# 2dolvlBUP.net
KiCad netlist of a schematic drawn in EAGLE
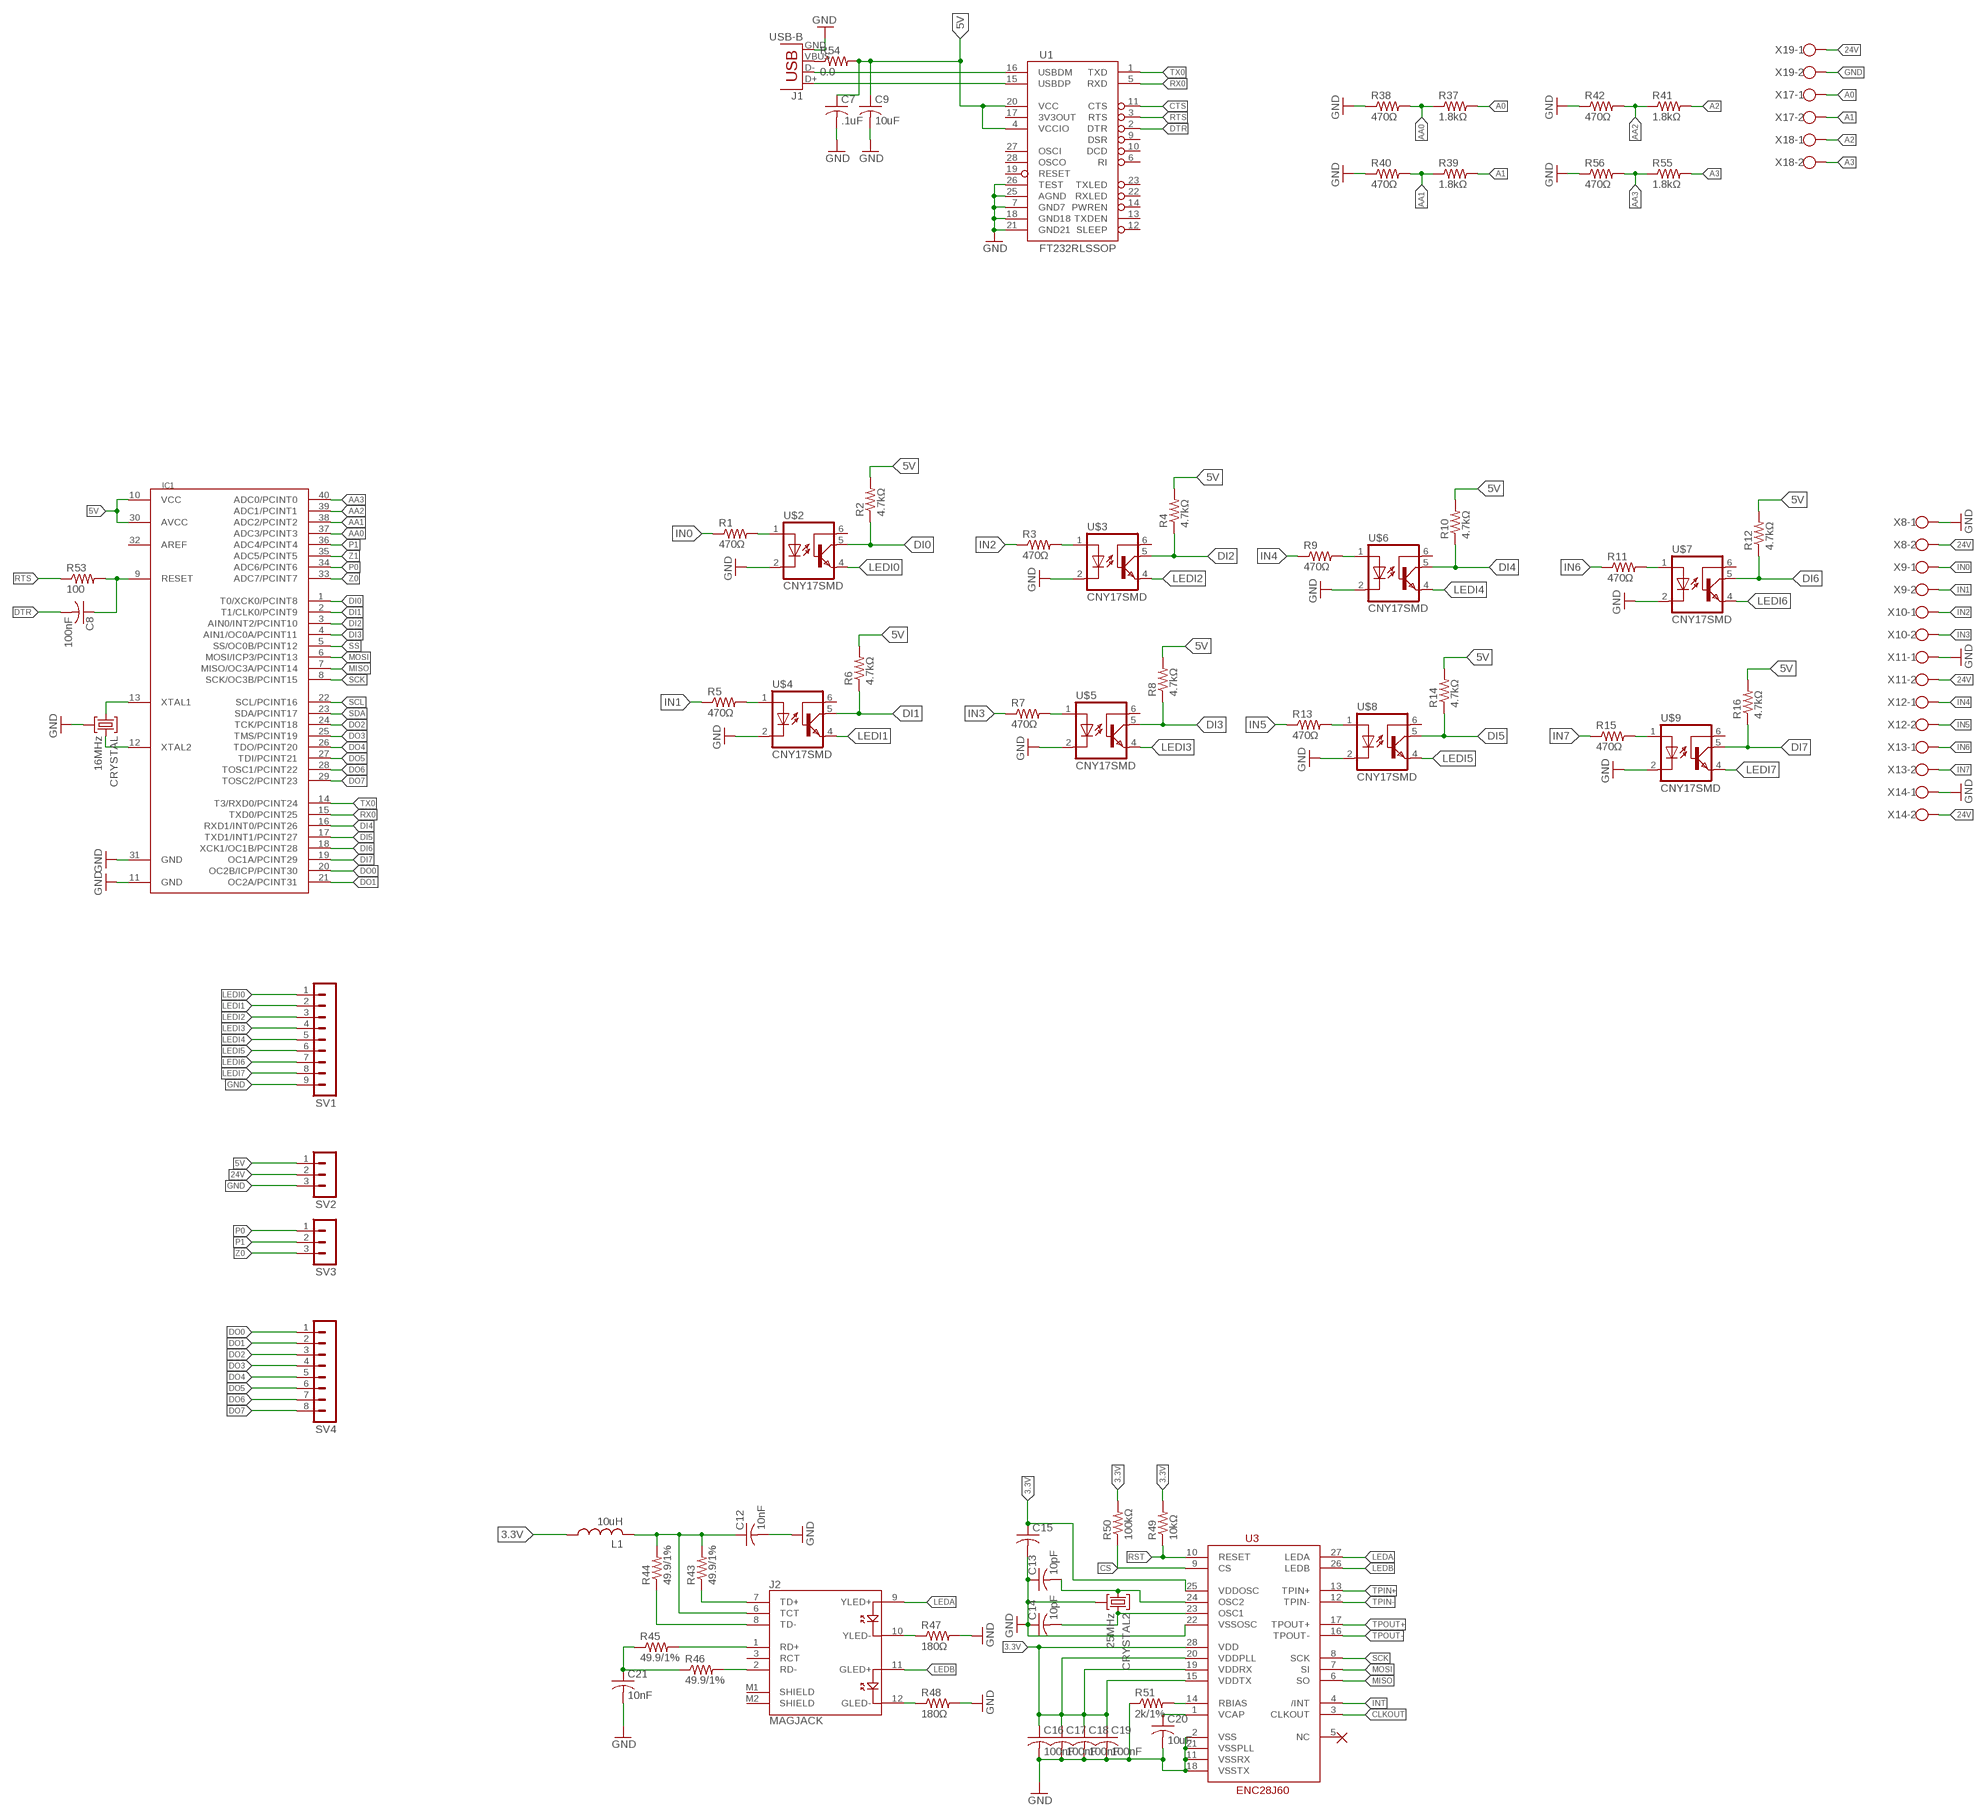
[diagram p0: schematic, sheet 1]

(export (version "E")
  (design (tool "Eeschema 10.0.6"))
  (components
    (comp (ref "C7")
      (value ".1uF")
      (footprint "eagle-import:C0402K")
      (libsource (lib "eagle-import") (part "C-USC0402K"))
    )
    (comp (ref "C8")
      (value "100nF")
      (footprint "eagle-import:C025-025X050")
      (libsource (lib "eagle-import") (part "C-US025-025X050"))
    )
    (comp (ref "C9")
      (value "10uF")
      (footprint "eagle-import:C0805K")
      (libsource (lib "eagle-import") (part "C-USC0805K"))
    )
    (comp (ref "C12")
      (value "10nF")
      (footprint "eagle-import:C0402K")
      (libsource (lib "eagle-import") (part "C-USC0402K"))
    )
    (comp (ref "C13")
      (value "10pF")
      (footprint "eagle-import:C0603K")
      (libsource (lib "eagle-import") (part "C-USC0603K"))
    )
    (comp (ref "C14")
      (value "10pF")
      (footprint "eagle-import:C0603K")
      (libsource (lib "eagle-import") (part "C-USC0603K"))
    )
    (comp (ref "C15")
      (value "C-US025-025X050")
      (footprint "eagle-import:C025-025X050")
      (libsource (lib "eagle-import") (part "C-US025-025X050"))
    )
    (comp (ref "C16")
      (value "100nF")
      (footprint "eagle-import:C025-025X050")
      (libsource (lib "eagle-import") (part "C-US025-025X050"))
    )
    (comp (ref "C17")
      (value "100nF")
      (footprint "eagle-import:C025-025X050")
      (libsource (lib "eagle-import") (part "C-US025-025X050"))
    )
    (comp (ref "C18")
      (value "100nF")
      (footprint "eagle-import:C025-025X050")
      (libsource (lib "eagle-import") (part "C-US025-025X050"))
    )
    (comp (ref "C19")
      (value "100nF")
      (footprint "eagle-import:C025-025X050")
      (libsource (lib "eagle-import") (part "C-US025-025X050"))
    )
    (comp (ref "C20")
      (value "10uF")
      (footprint "eagle-import:C0805K")
      (libsource (lib "eagle-import") (part "C-USC0805K"))
    )
    (comp (ref "C21")
      (value "10nF")
      (footprint "eagle-import:C0402K")
      (libsource (lib "eagle-import") (part "C-USC0402K"))
    )
    (comp (ref "CRYSTAL")
      (value "16MHz")
      (footprint "eagle-import:SMDCRYSTAL")
      (libsource (lib "eagle-import") (part "SMDCRYSTAL"))
    )
    (comp (ref "CRYSTAL2")
      (value "25MHz")
      (footprint "eagle-import:SMDCRYSTAL")
      (libsource (lib "eagle-import") (part "SMDCRYSTAL"))
    )
    (comp (ref "IC1")
      (value "MEGA1284P")
      (footprint "eagle-import:DIL40")
      (libsource (lib "eagle-import") (part "MEGA1284P"))
    )
    (comp (ref "J1")
      (value "USB-B")
      (footprint "eagle-import:USB-B-PTH")
      (libsource (lib "eagle-import") (part "USBPTH"))
    )
    (comp (ref "J2")
      (value "MAGJACK")
      (footprint "eagle-import:MAGJACK")
      (libsource (lib "eagle-import") (part "MAGJACK"))
    )
    (comp (ref "L1")
      (value "10uH")
      (footprint "eagle-import:0204_7")
      (libsource (lib "eagle-import") (part "L-US0204/7"))
    )
    (comp (ref "R1")
      (value "470Ω")
      (footprint "eagle-import:M0805")
      (libsource (lib "eagle-import") (part "R-US_M0805"))
    )
    (comp (ref "R2")
      (value "4.7kΩ")
      (footprint "eagle-import:M1206")
      (libsource (lib "eagle-import") (part "R-US_M1206"))
    )
    (comp (ref "R3")
      (value "470Ω")
      (footprint "eagle-import:M0805")
      (libsource (lib "eagle-import") (part "R-US_M0805"))
    )
    (comp (ref "R4")
      (value "4.7kΩ")
      (footprint "eagle-import:M1206")
      (libsource (lib "eagle-import") (part "R-US_M1206"))
    )
    (comp (ref "R5")
      (value "470Ω")
      (footprint "eagle-import:M0805")
      (libsource (lib "eagle-import") (part "R-US_M0805"))
    )
    (comp (ref "R6")
      (value "4.7kΩ")
      (footprint "eagle-import:M1206")
      (libsource (lib "eagle-import") (part "R-US_M1206"))
    )
    (comp (ref "R7")
      (value "470Ω")
      (footprint "eagle-import:M0805")
      (libsource (lib "eagle-import") (part "R-US_M0805"))
    )
    (comp (ref "R8")
      (value "4.7kΩ")
      (footprint "eagle-import:M1206")
      (libsource (lib "eagle-import") (part "R-US_M1206"))
    )
    (comp (ref "R9")
      (value "470Ω")
      (footprint "eagle-import:M0805")
      (libsource (lib "eagle-import") (part "R-US_M0805"))
    )
    (comp (ref "R10")
      (value "4.7kΩ")
      (footprint "eagle-import:M1206")
      (libsource (lib "eagle-import") (part "R-US_M1206"))
    )
    (comp (ref "R11")
      (value "470Ω")
      (footprint "eagle-import:M0805")
      (libsource (lib "eagle-import") (part "R-US_M0805"))
    )
    (comp (ref "R12")
      (value "4.7kΩ")
      (footprint "eagle-import:M1206")
      (libsource (lib "eagle-import") (part "R-US_M1206"))
    )
    (comp (ref "R13")
      (value "470Ω")
      (footprint "eagle-import:M0805")
      (libsource (lib "eagle-import") (part "R-US_M0805"))
    )
    (comp (ref "R14")
      (value "4.7kΩ")
      (footprint "eagle-import:M1206")
      (libsource (lib "eagle-import") (part "R-US_M1206"))
    )
    (comp (ref "R15")
      (value "470Ω")
      (footprint "eagle-import:M0805")
      (libsource (lib "eagle-import") (part "R-US_M0805"))
    )
    (comp (ref "R16")
      (value "4.7kΩ")
      (footprint "eagle-import:M1206")
      (libsource (lib "eagle-import") (part "R-US_M1206"))
    )
    (comp (ref "R37")
      (value "1.8kΩ")
      (footprint "eagle-import:M0805")
      (libsource (lib "eagle-import") (part "R-US_M0805"))
    )
    (comp (ref "R38")
      (value "470Ω")
      (footprint "eagle-import:M0805")
      (libsource (lib "eagle-import") (part "R-US_M0805"))
    )
    (comp (ref "R39")
      (value "1.8kΩ")
      (footprint "eagle-import:M0805")
      (libsource (lib "eagle-import") (part "R-US_M0805"))
    )
    (comp (ref "R40")
      (value "470Ω")
      (footprint "eagle-import:M0805")
      (libsource (lib "eagle-import") (part "R-US_M0805"))
    )
    (comp (ref "R41")
      (value "1.8kΩ")
      (footprint "eagle-import:M0805")
      (libsource (lib "eagle-import") (part "R-US_M0805"))
    )
    (comp (ref "R42")
      (value "470Ω")
      (footprint "eagle-import:M0805")
      (libsource (lib "eagle-import") (part "R-US_M0805"))
    )
    (comp (ref "R43")
      (value "49.9/1%")
      (footprint "eagle-import:R0402")
      (libsource (lib "eagle-import") (part "R-US_R0402"))
    )
    (comp (ref "R44")
      (value "49.9/1%")
      (footprint "eagle-import:R0402")
      (libsource (lib "eagle-import") (part "R-US_R0402"))
    )
    (comp (ref "R45")
      (value "49.9/1%")
      (footprint "eagle-import:R0402")
      (libsource (lib "eagle-import") (part "R-US_R0402"))
    )
    (comp (ref "R46")
      (value "49.9/1%")
      (footprint "eagle-import:R0402")
      (libsource (lib "eagle-import") (part "R-US_R0402"))
    )
    (comp (ref "R47")
      (value "180Ω")
      (footprint "eagle-import:M0805")
      (libsource (lib "eagle-import") (part "R-US_M0805"))
    )
    (comp (ref "R48")
      (value "180Ω")
      (footprint "eagle-import:M0805")
      (libsource (lib "eagle-import") (part "R-US_M0805"))
    )
    (comp (ref "R49")
      (value "10kΩ")
      (footprint "eagle-import:R0402")
      (libsource (lib "eagle-import") (part "R-US_R0402"))
    )
    (comp (ref "R50")
      (value "100kΩ")
      (footprint "eagle-import:R0603")
      (libsource (lib "eagle-import") (part "R-US_R0603"))
    )
    (comp (ref "R51")
      (value "2k/1%")
      (footprint "eagle-import:R0603")
      (libsource (lib "eagle-import") (part "R-US_R0603"))
    )
    (comp (ref "R53")
      (value "100")
      (footprint "eagle-import:1206")
      (libsource (lib "eagle-import") (part "RESISTOR1206"))
    )
    (comp (ref "R54")
      (value "0.0")
      (footprint "eagle-import:1206")
      (libsource (lib "eagle-import") (part "RESISTOR1206"))
    )
    (comp (ref "R55")
      (value "1.8kΩ")
      (footprint "eagle-import:M0805")
      (libsource (lib "eagle-import") (part "R-US_M0805"))
    )
    (comp (ref "R56")
      (value "470Ω")
      (footprint "eagle-import:M0805")
      (libsource (lib "eagle-import") (part "R-US_M0805"))
    )
    (comp (ref "SV1")
      (value "MA09-1")
      (footprint "eagle-import:MA09-1")
      (libsource (lib "eagle-import") (part "MA09-1"))
    )
    (comp (ref "SV2")
      (value "MA03-1")
      (footprint "eagle-import:MA03-1")
      (libsource (lib "eagle-import") (part "MA03-1"))
    )
    (comp (ref "SV3")
      (value "MA03-1")
      (footprint "eagle-import:MA03-1")
      (libsource (lib "eagle-import") (part "MA03-1"))
    )
    (comp (ref "SV4")
      (value "MA08-1")
      (footprint "eagle-import:MA08-1")
      (libsource (lib "eagle-import") (part "MA08-1"))
    )
    (comp (ref "U$2")
      (value "CNY17SMD")
      (footprint "eagle-import:DIL6-SMD")
      (libsource (lib "eagle-import") (part "CNY17SMD"))
    )
    (comp (ref "U$3")
      (value "CNY17SMD")
      (footprint "eagle-import:DIL6-SMD")
      (libsource (lib "eagle-import") (part "CNY17SMD"))
    )
    (comp (ref "U$4")
      (value "CNY17SMD")
      (footprint "eagle-import:DIL6-SMD")
      (libsource (lib "eagle-import") (part "CNY17SMD"))
    )
    (comp (ref "U$5")
      (value "CNY17SMD")
      (footprint "eagle-import:DIL6-SMD")
      (libsource (lib "eagle-import") (part "CNY17SMD"))
    )
    (comp (ref "U$6")
      (value "CNY17SMD")
      (footprint "eagle-import:DIL6-SMD")
      (libsource (lib "eagle-import") (part "CNY17SMD"))
    )
    (comp (ref "U$7")
      (value "CNY17SMD")
      (footprint "eagle-import:DIL6-SMD")
      (libsource (lib "eagle-import") (part "CNY17SMD"))
    )
    (comp (ref "U$8")
      (value "CNY17SMD")
      (footprint "eagle-import:DIL6-SMD")
      (libsource (lib "eagle-import") (part "CNY17SMD"))
    )
    (comp (ref "U$9")
      (value "CNY17SMD")
      (footprint "eagle-import:DIL6-SMD")
      (libsource (lib "eagle-import") (part "CNY17SMD"))
    )
    (comp (ref "U1")
      (value "FT232RLSSOP")
      (footprint "eagle-import:SSOP28DB")
      (libsource (lib "eagle-import") (part "FT232RLSSOP"))
    )
    (comp (ref "U3")
      (value "ENC28J60")
      (footprint "eagle-import:SSOP28DB")
      (libsource (lib "eagle-import") (part "ENC28J60"))
    )
    (comp (ref "X8")
      (value "W237-102")
      (footprint "eagle-import:W237-102")
      (fields (field (name "MPN") "237-102"))
      (libsource (lib "eagle-import") (part "W237-102"))
    )
    (comp (ref "X9")
      (value "W237-102")
      (footprint "eagle-import:W237-102")
      (fields (field (name "MPN") "237-102"))
      (libsource (lib "eagle-import") (part "W237-102"))
    )
    (comp (ref "X10")
      (value "W237-102")
      (footprint "eagle-import:W237-102")
      (fields (field (name "MPN") "237-102"))
      (libsource (lib "eagle-import") (part "W237-102"))
    )
    (comp (ref "X11")
      (value "W237-102")
      (footprint "eagle-import:W237-102")
      (fields (field (name "MPN") "237-102"))
      (libsource (lib "eagle-import") (part "W237-102"))
    )
    (comp (ref "X12")
      (value "W237-102")
      (footprint "eagle-import:W237-102")
      (fields (field (name "MPN") "237-102"))
      (libsource (lib "eagle-import") (part "W237-102"))
    )
    (comp (ref "X13")
      (value "W237-102")
      (footprint "eagle-import:W237-102")
      (fields (field (name "MPN") "237-102"))
      (libsource (lib "eagle-import") (part "W237-102"))
    )
    (comp (ref "X14")
      (value "W237-102")
      (footprint "eagle-import:W237-102")
      (fields (field (name "MPN") "237-102"))
      (libsource (lib "eagle-import") (part "W237-102"))
    )
    (comp (ref "X17")
      (value "W237-102")
      (footprint "eagle-import:W237-102")
      (fields (field (name "MPN") "237-102"))
      (libsource (lib "eagle-import") (part "W237-102"))
    )
    (comp (ref "X18")
      (value "W237-102")
      (footprint "eagle-import:W237-102")
      (fields (field (name "MPN") "237-102"))
      (libsource (lib "eagle-import") (part "W237-102"))
    )
    (comp (ref "X19")
      (value "W237-102")
      (footprint "eagle-import:W237-102")
      (fields (field (name "MPN") "237-102"))
      (libsource (lib "eagle-import") (part "W237-102"))
    )
  )
  (nets
    (net (code "1") (name "3.3V") (class "Default")
      (node (ref "C15") (pin "1") (pinfunction "1_1") (pintype "passive"))
      (node (ref "C16") (pin "1") (pinfunction "1_1") (pintype "passive"))
      (node (ref "C17") (pin "1") (pinfunction "1_1") (pintype "passive"))
      (node (ref "C18") (pin "1") (pinfunction "1_1") (pintype "passive"))
      (node (ref "C19") (pin "1") (pinfunction "1_1") (pintype "passive"))
      (node (ref "L1") (pin "1") (pinfunction "1_1") (pintype "passive"))
      (node (ref "R49") (pin "2") (pinfunction "2_2") (pintype "passive"))
      (node (ref "R50") (pin "2") (pinfunction "2_2") (pintype "passive"))
      (node (ref "U3") (pin "15") (pinfunction "VDDTX_15") (pintype "bidirectional"))
      (node (ref "U3") (pin "19") (pinfunction "VDDRX_19") (pintype "bidirectional"))
      (node (ref "U3") (pin "20") (pinfunction "VDDPLL_20") (pintype "bidirectional"))
      (node (ref "U3") (pin "25") (pinfunction "VDDOSC_25") (pintype "bidirectional"))
      (node (ref "U3") (pin "28") (pinfunction "VDD_28") (pintype "bidirectional"))
    )
    (net (code "2") (name "5V") (class "Default")
      (node (ref "C7") (pin "1") (pinfunction "1_1") (pintype "passive"))
      (node (ref "C9") (pin "1") (pinfunction "1_1") (pintype "passive"))
      (node (ref "IC1") (pin "10") (pinfunction "VCC_10") (pintype "bidirectional"))
      (node (ref "IC1") (pin "30") (pinfunction "AVCC_30") (pintype "bidirectional"))
      (node (ref "R10") (pin "2") (pinfunction "2_2") (pintype "passive"))
      (node (ref "R12") (pin "2") (pinfunction "2_2") (pintype "passive"))
      (node (ref "R14") (pin "2") (pinfunction "2_2") (pintype "passive"))
      (node (ref "R16") (pin "2") (pinfunction "2_2") (pintype "passive"))
      (node (ref "R2") (pin "2") (pinfunction "2_2") (pintype "passive"))
      (node (ref "R4") (pin "2") (pinfunction "2_2") (pintype "passive"))
      (node (ref "R54") (pin "2") (pinfunction "2_2") (pintype "passive"))
      (node (ref "R6") (pin "2") (pinfunction "2_2") (pintype "passive"))
      (node (ref "R8") (pin "2") (pinfunction "2_2") (pintype "passive"))
      (node (ref "SV2") (pin "1") (pinfunction "1_1") (pintype "passive"))
      (node (ref "U1") (pin "20") (pinfunction "VCC_20") (pintype "power_in"))
      (node (ref "U1") (pin "4") (pinfunction "VCCIO_4") (pintype "power_in"))
    )
    (net (code "3") (name "24V") (class "Default")
      (node (ref "SV2") (pin "2") (pinfunction "2_2") (pintype "passive"))
      (node (ref "X11") (pin "2") (pinfunction "KL_2") (pintype "passive"))
      (node (ref "X14") (pin "2") (pinfunction "KL_2") (pintype "passive"))
      (node (ref "X19") (pin "1") (pinfunction "KL_1") (pintype "passive"))
      (node (ref "X8") (pin "2") (pinfunction "KL_2") (pintype "passive"))
    )
    (net (code "4") (name "A0") (class "Default")
      (node (ref "R37") (pin "2") (pinfunction "2_2") (pintype "passive"))
      (node (ref "X17") (pin "1") (pinfunction "KL_1") (pintype "passive"))
    )
    (net (code "5") (name "A1") (class "Default")
      (node (ref "R39") (pin "2") (pinfunction "2_2") (pintype "passive"))
      (node (ref "X17") (pin "2") (pinfunction "KL_2") (pintype "passive"))
    )
    (net (code "6") (name "A2") (class "Default")
      (node (ref "R41") (pin "2") (pinfunction "2_2") (pintype "passive"))
      (node (ref "X18") (pin "1") (pinfunction "KL_1") (pintype "passive"))
    )
    (net (code "7") (name "A3") (class "Default")
      (node (ref "R55") (pin "2") (pinfunction "2_2") (pintype "passive"))
      (node (ref "X18") (pin "2") (pinfunction "KL_2") (pintype "passive"))
    )
    (net (code "8") (name "AA0") (class "Default")
      (node (ref "IC1") (pin "37") (pinfunction "ADC3/PCINT3_37") (pintype "bidirectional"))
      (node (ref "R37") (pin "1") (pinfunction "1_1") (pintype "passive"))
      (node (ref "R38") (pin "2") (pinfunction "2_2") (pintype "passive"))
    )
    (net (code "9") (name "AA1") (class "Default")
      (node (ref "IC1") (pin "38") (pinfunction "ADC2/PCINT2_38") (pintype "bidirectional"))
      (node (ref "R39") (pin "1") (pinfunction "1_1") (pintype "passive"))
      (node (ref "R40") (pin "2") (pinfunction "2_2") (pintype "passive"))
    )
    (net (code "10") (name "AA2") (class "Default")
      (node (ref "IC1") (pin "39") (pinfunction "ADC1/PCINT1_39") (pintype "bidirectional"))
      (node (ref "R41") (pin "1") (pinfunction "1_1") (pintype "passive"))
      (node (ref "R42") (pin "2") (pinfunction "2_2") (pintype "passive"))
    )
    (net (code "11") (name "AA3") (class "Default")
      (node (ref "IC1") (pin "40") (pinfunction "ADC0/PCINT0_40") (pintype "bidirectional"))
      (node (ref "R55") (pin "1") (pinfunction "1_1") (pintype "passive"))
      (node (ref "R56") (pin "2") (pinfunction "2_2") (pintype "passive"))
    )
    (net (code "12") (name "CLKOUT") (class "Default")
      (node (ref "U3") (pin "3") (pinfunction "CLKOUT_3") (pintype "bidirectional"))
    )
    (net (code "13") (name "CS") (class "Default")
      (node (ref "R50") (pin "1") (pinfunction "1_1") (pintype "passive"))
      (node (ref "U3") (pin "9") (pinfunction "CS_9") (pintype "bidirectional"))
    )
    (net (code "14") (name "CTS") (class "Default")
      (node (ref "U1") (pin "11") (pinfunction "CTS_11") (pintype "input"))
    )
    (net (code "15") (name "DI0") (class "Default")
      (node (ref "IC1") (pin "1") (pinfunction "T0/XCK0/PCINT8_1") (pintype "bidirectional"))
      (node (ref "R2") (pin "1") (pinfunction "1_1") (pintype "passive"))
      (node (ref "U$2") (pin "5") (pinfunction "COL_5") (pintype "passive"))
    )
    (net (code "16") (name "DI1") (class "Default")
      (node (ref "IC1") (pin "2") (pinfunction "T1/CLK0/PCINT9_2") (pintype "bidirectional"))
      (node (ref "R6") (pin "1") (pinfunction "1_1") (pintype "passive"))
      (node (ref "U$4") (pin "5") (pinfunction "COL_5") (pintype "passive"))
    )
    (net (code "17") (name "DI2") (class "Default")
      (node (ref "IC1") (pin "3") (pinfunction "AIN0/INT2/PCINT10_3") (pintype "bidirectional"))
      (node (ref "R4") (pin "1") (pinfunction "1_1") (pintype "passive"))
      (node (ref "U$3") (pin "5") (pinfunction "COL_5") (pintype "passive"))
    )
    (net (code "18") (name "DI3") (class "Default")
      (node (ref "IC1") (pin "4") (pinfunction "AIN1/OC0A/PCINT11_4") (pintype "bidirectional"))
      (node (ref "R8") (pin "1") (pinfunction "1_1") (pintype "passive"))
      (node (ref "U$5") (pin "5") (pinfunction "COL_5") (pintype "passive"))
    )
    (net (code "19") (name "DI4") (class "Default")
      (node (ref "IC1") (pin "16") (pinfunction "RXD1/INT0/PCINT26_16") (pintype "bidirectional"))
      (node (ref "R10") (pin "1") (pinfunction "1_1") (pintype "passive"))
      (node (ref "U$6") (pin "5") (pinfunction "COL_5") (pintype "passive"))
    )
    (net (code "20") (name "DI5") (class "Default")
      (node (ref "IC1") (pin "17") (pinfunction "TXD1/INT1/PCINT27_17") (pintype "bidirectional"))
      (node (ref "R14") (pin "1") (pinfunction "1_1") (pintype "passive"))
      (node (ref "U$8") (pin "5") (pinfunction "COL_5") (pintype "passive"))
    )
    (net (code "21") (name "DI6") (class "Default")
      (node (ref "IC1") (pin "18") (pinfunction "XCK1/OC1B/PCINT28_18") (pintype "bidirectional"))
      (node (ref "R12") (pin "1") (pinfunction "1_1") (pintype "passive"))
      (node (ref "U$7") (pin "5") (pinfunction "COL_5") (pintype "passive"))
    )
    (net (code "22") (name "DI7") (class "Default")
      (node (ref "IC1") (pin "19") (pinfunction "OC1A/PCINT29_19") (pintype "bidirectional"))
      (node (ref "R16") (pin "1") (pinfunction "1_1") (pintype "passive"))
      (node (ref "U$9") (pin "5") (pinfunction "COL_5") (pintype "passive"))
    )
    (net (code "23") (name "DO0") (class "Default")
      (node (ref "IC1") (pin "20") (pinfunction "OC2B/ICP/PCINT30_20") (pintype "bidirectional"))
      (node (ref "SV4") (pin "1") (pinfunction "1_1") (pintype "passive"))
    )
    (net (code "24") (name "DO1") (class "Default")
      (node (ref "IC1") (pin "21") (pinfunction "OC2A/PCINT31_21") (pintype "bidirectional"))
      (node (ref "SV4") (pin "2") (pinfunction "2_2") (pintype "passive"))
    )
    (net (code "25") (name "DO2") (class "Default")
      (node (ref "IC1") (pin "24") (pinfunction "TCK/PCINT18_24") (pintype "bidirectional"))
      (node (ref "SV4") (pin "3") (pinfunction "3_3") (pintype "passive"))
    )
    (net (code "26") (name "DO3") (class "Default")
      (node (ref "IC1") (pin "25") (pinfunction "TMS/PCINT19_25") (pintype "bidirectional"))
      (node (ref "SV4") (pin "4") (pinfunction "4_4") (pintype "passive"))
    )
    (net (code "27") (name "DO4") (class "Default")
      (node (ref "IC1") (pin "26") (pinfunction "TDO/PCINT20_26") (pintype "bidirectional"))
      (node (ref "SV4") (pin "5") (pinfunction "5_5") (pintype "passive"))
    )
    (net (code "28") (name "DO5") (class "Default")
      (node (ref "IC1") (pin "27") (pinfunction "TDI/PCINT21_27") (pintype "bidirectional"))
      (node (ref "SV4") (pin "6") (pinfunction "6_6") (pintype "passive"))
    )
    (net (code "29") (name "DO6") (class "Default")
      (node (ref "IC1") (pin "28") (pinfunction "TOSC1/PCINT22_28") (pintype "bidirectional"))
      (node (ref "SV4") (pin "7") (pinfunction "7_7") (pintype "passive"))
    )
    (net (code "30") (name "DO7") (class "Default")
      (node (ref "IC1") (pin "29") (pinfunction "TOSC2/PCINT23_29") (pintype "bidirectional"))
      (node (ref "SV4") (pin "8") (pinfunction "8_8") (pintype "passive"))
    )
    (net (code "31") (name "DTR") (class "Default")
      (node (ref "C8") (pin "2") (pinfunction "2_2") (pintype "passive"))
      (node (ref "U1") (pin "2") (pinfunction "DTR_2") (pintype "output"))
    )
    (net (code "32") (name "GND") (class "Default")
      (node (ref "C12") (pin "2") (pinfunction "2_2") (pintype "passive"))
      (node (ref "C13") (pin "1") (pinfunction "1_1") (pintype "passive"))
      (node (ref "C14") (pin "1") (pinfunction "1_1") (pintype "passive"))
      (node (ref "C15") (pin "2") (pinfunction "2_2") (pintype "passive"))
      (node (ref "C16") (pin "2") (pinfunction "2_2") (pintype "passive"))
      (node (ref "C17") (pin "2") (pinfunction "2_2") (pintype "passive"))
      (node (ref "C18") (pin "2") (pinfunction "2_2") (pintype "passive"))
      (node (ref "C19") (pin "2") (pinfunction "2_2") (pintype "passive"))
      (node (ref "C20") (pin "2") (pinfunction "2_2") (pintype "passive"))
      (node (ref "C21") (pin "2") (pinfunction "2_2") (pintype "passive"))
      (node (ref "C7") (pin "2") (pinfunction "2_2") (pintype "passive"))
      (node (ref "C9") (pin "2") (pinfunction "2_2") (pintype "passive"))
      (node (ref "CRYSTAL") (pin "GND") (pinfunction "2_GND") (pintype "passive"))
      (node (ref "CRYSTAL2") (pin "GND") (pinfunction "2_GND") (pintype "passive"))
      (node (ref "IC1") (pin "11") (pinfunction "GND_11") (pintype "bidirectional"))
      (node (ref "IC1") (pin "31") (pinfunction "GND_31") (pintype "bidirectional"))
      (node (ref "J1") (pin "GND") (pinfunction "GND_GND") (pintype "bidirectional"))
      (node (ref "R38") (pin "1") (pinfunction "1_1") (pintype "passive"))
      (node (ref "R40") (pin "1") (pinfunction "1_1") (pintype "passive"))
      (node (ref "R42") (pin "1") (pinfunction "1_1") (pintype "passive"))
      (node (ref "R47") (pin "2") (pinfunction "2_2") (pintype "passive"))
      (node (ref "R48") (pin "2") (pinfunction "2_2") (pintype "passive"))
      (node (ref "R51") (pin "1") (pinfunction "1_1") (pintype "passive"))
      (node (ref "R56") (pin "1") (pinfunction "1_1") (pintype "passive"))
      (node (ref "SV1") (pin "9") (pinfunction "9_9") (pintype "passive"))
      (node (ref "SV2") (pin "3") (pinfunction "3_3") (pintype "passive"))
      (node (ref "U$2") (pin "2") (pinfunction "C_2") (pintype "passive"))
      (node (ref "U$3") (pin "2") (pinfunction "C_2") (pintype "passive"))
      (node (ref "U$4") (pin "2") (pinfunction "C_2") (pintype "passive"))
      (node (ref "U$5") (pin "2") (pinfunction "C_2") (pintype "passive"))
      (node (ref "U$6") (pin "2") (pinfunction "C_2") (pintype "passive"))
      (node (ref "U$7") (pin "2") (pinfunction "C_2") (pintype "passive"))
      (node (ref "U$8") (pin "2") (pinfunction "C_2") (pintype "passive"))
      (node (ref "U$9") (pin "2") (pinfunction "C_2") (pintype "passive"))
      (node (ref "U1") (pin "18") (pinfunction "GND18_18") (pintype "power_in"))
      (node (ref "U1") (pin "21") (pinfunction "GND21_21") (pintype "power_in"))
      (node (ref "U1") (pin "25") (pinfunction "AGND_25") (pintype "power_in"))
      (node (ref "U1") (pin "26") (pinfunction "TEST_26") (pintype "input"))
      (node (ref "U1") (pin "7") (pinfunction "GND7_7") (pintype "power_in"))
      (node (ref "U3") (pin "11") (pinfunction "VSSRX_11") (pintype "bidirectional"))
      (node (ref "U3") (pin "18") (pinfunction "VSSTX_18") (pintype "bidirectional"))
      (node (ref "U3") (pin "2") (pinfunction "VSS_2") (pintype "bidirectional"))
      (node (ref "U3") (pin "21") (pinfunction "VSSPLL_21") (pintype "bidirectional"))
      (node (ref "U3") (pin "22") (pinfunction "VSSOSC_22") (pintype "bidirectional"))
      (node (ref "X11") (pin "1") (pinfunction "KL_1") (pintype "passive"))
      (node (ref "X14") (pin "1") (pinfunction "KL_1") (pintype "passive"))
      (node (ref "X19") (pin "2") (pinfunction "KL_2") (pintype "passive"))
      (node (ref "X8") (pin "1") (pinfunction "KL_1") (pintype "passive"))
    )
    (net (code "33") (name "IN0") (class "Default")
      (node (ref "R1") (pin "1") (pinfunction "1_1") (pintype "passive"))
      (node (ref "X9") (pin "1") (pinfunction "KL_1") (pintype "passive"))
    )
    (net (code "34") (name "IN1") (class "Default")
      (node (ref "R5") (pin "1") (pinfunction "1_1") (pintype "passive"))
      (node (ref "X9") (pin "2") (pinfunction "KL_2") (pintype "passive"))
    )
    (net (code "35") (name "IN2") (class "Default")
      (node (ref "R3") (pin "1") (pinfunction "1_1") (pintype "passive"))
      (node (ref "X10") (pin "1") (pinfunction "KL_1") (pintype "passive"))
    )
    (net (code "36") (name "IN3") (class "Default")
      (node (ref "R7") (pin "1") (pinfunction "1_1") (pintype "passive"))
      (node (ref "X10") (pin "2") (pinfunction "KL_2") (pintype "passive"))
    )
    (net (code "37") (name "IN4") (class "Default")
      (node (ref "R9") (pin "1") (pinfunction "1_1") (pintype "passive"))
      (node (ref "X12") (pin "1") (pinfunction "KL_1") (pintype "passive"))
    )
    (net (code "38") (name "IN5") (class "Default")
      (node (ref "R13") (pin "1") (pinfunction "1_1") (pintype "passive"))
      (node (ref "X12") (pin "2") (pinfunction "KL_2") (pintype "passive"))
    )
    (net (code "39") (name "IN6") (class "Default")
      (node (ref "R11") (pin "1") (pinfunction "1_1") (pintype "passive"))
      (node (ref "X13") (pin "1") (pinfunction "KL_1") (pintype "passive"))
    )
    (net (code "40") (name "IN7") (class "Default")
      (node (ref "R15") (pin "1") (pinfunction "1_1") (pintype "passive"))
      (node (ref "X13") (pin "2") (pinfunction "KL_2") (pintype "passive"))
    )
    (net (code "41") (name "INT") (class "Default")
      (node (ref "U3") (pin "4") (pinfunction "/INT_4") (pintype "bidirectional"))
    )
    (net (code "42") (name "LEDA") (class "Default")
      (node (ref "J2") (pin "9") (pinfunction "YLED+_9") (pintype "bidirectional"))
      (node (ref "U3") (pin "27") (pinfunction "LEDA_27") (pintype "bidirectional"))
    )
    (net (code "43") (name "LEDB") (class "Default")
      (node (ref "J2") (pin "11") (pinfunction "GLED+_11") (pintype "bidirectional"))
      (node (ref "U3") (pin "26") (pinfunction "LEDB_26") (pintype "bidirectional"))
    )
    (net (code "44") (name "LEDI0") (class "Default")
      (node (ref "SV1") (pin "1") (pinfunction "1_1") (pintype "passive"))
      (node (ref "U$2") (pin "4") (pinfunction "EMI_4") (pintype "passive"))
    )
    (net (code "45") (name "LEDI1") (class "Default")
      (node (ref "SV1") (pin "2") (pinfunction "2_2") (pintype "passive"))
      (node (ref "U$4") (pin "4") (pinfunction "EMI_4") (pintype "passive"))
    )
    (net (code "46") (name "LEDI2") (class "Default")
      (node (ref "SV1") (pin "3") (pinfunction "3_3") (pintype "passive"))
      (node (ref "U$3") (pin "4") (pinfunction "EMI_4") (pintype "passive"))
    )
    (net (code "47") (name "LEDI3") (class "Default")
      (node (ref "SV1") (pin "4") (pinfunction "4_4") (pintype "passive"))
      (node (ref "U$5") (pin "4") (pinfunction "EMI_4") (pintype "passive"))
    )
    (net (code "48") (name "LEDI4") (class "Default")
      (node (ref "SV1") (pin "5") (pinfunction "5_5") (pintype "passive"))
      (node (ref "U$6") (pin "4") (pinfunction "EMI_4") (pintype "passive"))
    )
    (net (code "49") (name "LEDI5") (class "Default")
      (node (ref "SV1") (pin "6") (pinfunction "6_6") (pintype "passive"))
      (node (ref "U$8") (pin "4") (pinfunction "EMI_4") (pintype "passive"))
    )
    (net (code "50") (name "LEDI6") (class "Default")
      (node (ref "SV1") (pin "7") (pinfunction "7_7") (pintype "passive"))
      (node (ref "U$7") (pin "4") (pinfunction "EMI_4") (pintype "passive"))
    )
    (net (code "51") (name "LEDI7") (class "Default")
      (node (ref "SV1") (pin "8") (pinfunction "8_8") (pintype "passive"))
      (node (ref "U$9") (pin "4") (pinfunction "EMI_4") (pintype "passive"))
    )
    (net (code "52") (name "MISO") (class "Default")
      (node (ref "IC1") (pin "7") (pinfunction "MISO/OC3A/PCINT14_7") (pintype "bidirectional"))
      (node (ref "U3") (pin "6") (pinfunction "SO_6") (pintype "bidirectional"))
    )
    (net (code "53") (name "MOSI") (class "Default")
      (node (ref "IC1") (pin "6") (pinfunction "MOSI/ICP3/PCINT13_6") (pintype "bidirectional"))
      (node (ref "U3") (pin "7") (pinfunction "SI_7") (pintype "bidirectional"))
    )
    (net (code "54") (name "Net-(C21-Pad1)") (class "Default")
      (node (ref "C21") (pin "1") (pinfunction "1_1") (pintype "passive"))
      (node (ref "R45") (pin "1") (pinfunction "1_1") (pintype "passive"))
      (node (ref "R46") (pin "1") (pinfunction "1_1") (pintype "passive"))
    )
    (net (code "55") (name "Net-(CRYSTAL-3)") (class "Default")
      (node (ref "CRYSTAL") (pin "2") (pinfunction "3_2") (pintype "passive"))
      (node (ref "IC1") (pin "12") (pinfunction "XTAL2_12") (pintype "bidirectional"))
    )
    (net (code "56") (name "Net-(CRYSTAL2-3)") (class "Default")
      (node (ref "C14") (pin "2") (pinfunction "2_2") (pintype "passive"))
      (node (ref "CRYSTAL2") (pin "2") (pinfunction "3_2") (pintype "passive"))
      (node (ref "U3") (pin "23") (pinfunction "OSC1_23") (pintype "bidirectional"))
    )
    (net (code "57") (name "Net-(IC1-RESET)") (class "Default")
      (node (ref "C8") (pin "1") (pinfunction "1_1") (pintype "passive"))
      (node (ref "IC1") (pin "9") (pinfunction "RESET_9") (pintype "bidirectional"))
      (node (ref "R53") (pin "2") (pinfunction "2_2") (pintype "passive"))
    )
    (net (code "58") (name "Net-(IC1-XTAL1)") (class "Default")
      (node (ref "CRYSTAL") (pin "1") (pinfunction "1_1") (pintype "passive"))
      (node (ref "IC1") (pin "13") (pinfunction "XTAL1_13") (pintype "bidirectional"))
    )
    (net (code "59") (name "Net-(J1-PadVBUS)") (class "Default")
      (node (ref "J1") (pin "VBUS") (pinfunction "VBUS_VBUS") (pintype "bidirectional"))
      (node (ref "R54") (pin "1") (pinfunction "1_1") (pintype "passive"))
    )
    (net (code "60") (name "Net-(J2-GLED-)") (class "Default")
      (node (ref "J2") (pin "12") (pinfunction "GLED-_12") (pintype "bidirectional"))
      (node (ref "R48") (pin "1") (pinfunction "1_1") (pintype "passive"))
    )
    (net (code "61") (name "Net-(J2-RD+)") (class "Default")
      (node (ref "J2") (pin "1") (pinfunction "RD+_1") (pintype "bidirectional"))
      (node (ref "R45") (pin "2") (pinfunction "2_2") (pintype "passive"))
    )
    (net (code "62") (name "Net-(J2-RD-)") (class "Default")
      (node (ref "J2") (pin "2") (pinfunction "RD-_2") (pintype "bidirectional"))
      (node (ref "R46") (pin "2") (pinfunction "2_2") (pintype "passive"))
    )
    (net (code "63") (name "Net-(J2-TCT)") (class "Default")
      (node (ref "C12") (pin "1") (pinfunction "1_1") (pintype "passive"))
      (node (ref "J2") (pin "6") (pinfunction "TCT_6") (pintype "bidirectional"))
      (node (ref "L1") (pin "2") (pinfunction "2_2") (pintype "passive"))
      (node (ref "R43") (pin "2") (pinfunction "2_2") (pintype "passive"))
      (node (ref "R44") (pin "2") (pinfunction "2_2") (pintype "passive"))
    )
    (net (code "64") (name "Net-(J2-TD+)") (class "Default")
      (node (ref "J2") (pin "7") (pinfunction "TD+_7") (pintype "bidirectional"))
      (node (ref "R43") (pin "1") (pinfunction "1_1") (pintype "passive"))
    )
    (net (code "65") (name "Net-(J2-TD-)") (class "Default")
      (node (ref "J2") (pin "8") (pinfunction "TD-_8") (pintype "bidirectional"))
      (node (ref "R44") (pin "1") (pinfunction "1_1") (pintype "passive"))
    )
    (net (code "66") (name "Net-(J2-YLED-)") (class "Default")
      (node (ref "J2") (pin "10") (pinfunction "YLED-_10") (pintype "bidirectional"))
      (node (ref "R47") (pin "1") (pinfunction "1_1") (pintype "passive"))
    )
    (net (code "67") (name "Net-(U$2-A)") (class "Default")
      (node (ref "R1") (pin "2") (pinfunction "2_2") (pintype "passive"))
      (node (ref "U$2") (pin "1") (pinfunction "A_1") (pintype "passive"))
    )
    (net (code "68") (name "Net-(U$3-A)") (class "Default")
      (node (ref "R3") (pin "2") (pinfunction "2_2") (pintype "passive"))
      (node (ref "U$3") (pin "1") (pinfunction "A_1") (pintype "passive"))
    )
    (net (code "69") (name "Net-(U$4-A)") (class "Default")
      (node (ref "R5") (pin "2") (pinfunction "2_2") (pintype "passive"))
      (node (ref "U$4") (pin "1") (pinfunction "A_1") (pintype "passive"))
    )
    (net (code "70") (name "Net-(U$5-A)") (class "Default")
      (node (ref "R7") (pin "2") (pinfunction "2_2") (pintype "passive"))
      (node (ref "U$5") (pin "1") (pinfunction "A_1") (pintype "passive"))
    )
    (net (code "71") (name "Net-(U$6-A)") (class "Default")
      (node (ref "R9") (pin "2") (pinfunction "2_2") (pintype "passive"))
      (node (ref "U$6") (pin "1") (pinfunction "A_1") (pintype "passive"))
    )
    (net (code "72") (name "Net-(U$7-A)") (class "Default")
      (node (ref "R11") (pin "2") (pinfunction "2_2") (pintype "passive"))
      (node (ref "U$7") (pin "1") (pinfunction "A_1") (pintype "passive"))
    )
    (net (code "73") (name "Net-(U$8-A)") (class "Default")
      (node (ref "R13") (pin "2") (pinfunction "2_2") (pintype "passive"))
      (node (ref "U$8") (pin "1") (pinfunction "A_1") (pintype "passive"))
    )
    (net (code "74") (name "Net-(U$9-A)") (class "Default")
      (node (ref "R15") (pin "2") (pinfunction "2_2") (pintype "passive"))
      (node (ref "U$9") (pin "1") (pinfunction "A_1") (pintype "passive"))
    )
    (net (code "75") (name "Net-(U1-USBDM)") (class "Default")
      (node (ref "J1") (pin "D-") (pinfunction "D-_D-") (pintype "bidirectional"))
      (node (ref "U1") (pin "16") (pinfunction "USBDM_16") (pintype "bidirectional"))
    )
    (net (code "76") (name "Net-(U1-USBDP)") (class "Default")
      (node (ref "J1") (pin "D+") (pinfunction "D+_D+") (pintype "bidirectional"))
      (node (ref "U1") (pin "15") (pinfunction "USBDP_15") (pintype "bidirectional"))
    )
    (net (code "77") (name "Net-(U3-OSC2)") (class "Default")
      (node (ref "C13") (pin "2") (pinfunction "2_2") (pintype "passive"))
      (node (ref "CRYSTAL2") (pin "1") (pinfunction "1_1") (pintype "passive"))
      (node (ref "U3") (pin "24") (pinfunction "OSC2_24") (pintype "bidirectional"))
    )
    (net (code "78") (name "Net-(U3-RBIAS)") (class "Default")
      (node (ref "R51") (pin "2") (pinfunction "2_2") (pintype "passive"))
      (node (ref "U3") (pin "14") (pinfunction "RBIAS_14") (pintype "bidirectional"))
    )
    (net (code "79") (name "Net-(U3-VCAP)") (class "Default")
      (node (ref "C20") (pin "1") (pinfunction "1_1") (pintype "passive"))
      (node (ref "U3") (pin "1") (pinfunction "VCAP_1") (pintype "bidirectional"))
    )
    (net (code "80") (name "P0") (class "Default")
      (node (ref "IC1") (pin "34") (pinfunction "ADC6/PCINT6_34") (pintype "bidirectional"))
      (node (ref "SV3") (pin "1") (pinfunction "1_1") (pintype "passive"))
    )
    (net (code "81") (name "P1") (class "Default")
      (node (ref "IC1") (pin "36") (pinfunction "ADC4/PCINT4_36") (pintype "bidirectional"))
      (node (ref "SV3") (pin "2") (pinfunction "2_2") (pintype "passive"))
    )
    (net (code "82") (name "RST") (class "Default")
      (node (ref "R49") (pin "1") (pinfunction "1_1") (pintype "passive"))
      (node (ref "U3") (pin "10") (pinfunction "RESET_10") (pintype "bidirectional"))
    )
    (net (code "83") (name "RTS") (class "Default")
      (node (ref "R53") (pin "1") (pinfunction "1_1") (pintype "passive"))
      (node (ref "U1") (pin "3") (pinfunction "RTS_3") (pintype "output"))
    )
    (net (code "84") (name "RX0") (class "Default")
      (node (ref "IC1") (pin "15") (pinfunction "TXD0/PCINT25_15") (pintype "bidirectional"))
      (node (ref "U1") (pin "5") (pinfunction "RXD_5") (pintype "input"))
    )
    (net (code "85") (name "SCK") (class "Default")
      (node (ref "IC1") (pin "8") (pinfunction "SCK/OC3B/PCINT15_8") (pintype "bidirectional"))
      (node (ref "U3") (pin "8") (pinfunction "SCK_8") (pintype "bidirectional"))
    )
    (net (code "86") (name "SCL") (class "Default")
      (node (ref "IC1") (pin "22") (pinfunction "SCL/PCINT16_22") (pintype "bidirectional"))
    )
    (net (code "87") (name "SDA") (class "Default")
      (node (ref "IC1") (pin "23") (pinfunction "SDA/PCINT17_23") (pintype "bidirectional"))
    )
    (net (code "88") (name "SS") (class "Default")
      (node (ref "IC1") (pin "5") (pinfunction "SS/OC0B/PCINT12_5") (pintype "bidirectional"))
    )
    (net (code "89") (name "TPIN+") (class "Default")
      (node (ref "U3") (pin "13") (pinfunction "TPIN+_13") (pintype "bidirectional"))
    )
    (net (code "90") (name "TPIN-") (class "Default")
      (node (ref "U3") (pin "12") (pinfunction "TPIN-_12") (pintype "bidirectional"))
    )
    (net (code "91") (name "TPOUT+") (class "Default")
      (node (ref "U3") (pin "17") (pinfunction "TPOUT+_17") (pintype "bidirectional"))
    )
    (net (code "92") (name "TPOUT-") (class "Default")
      (node (ref "U3") (pin "16") (pinfunction "TPOUT-_16") (pintype "bidirectional"))
    )
    (net (code "93") (name "TX0") (class "Default")
      (node (ref "IC1") (pin "14") (pinfunction "T3/RXD0/PCINT24_14") (pintype "bidirectional"))
      (node (ref "U1") (pin "1") (pinfunction "TXD_1") (pintype "output"))
    )
    (net (code "94") (name "Z0") (class "Default")
      (node (ref "IC1") (pin "33") (pinfunction "ADC7/PCINT7_33") (pintype "bidirectional"))
      (node (ref "SV3") (pin "3") (pinfunction "3_3") (pintype "passive"))
    )
    (net (code "95") (name "Z1") (class "Default")
      (node (ref "IC1") (pin "35") (pinfunction "ADC5/PCINT5_35") (pintype "bidirectional"))
    )
    (net (code "96") (name "unconnected-(IC1-AREF-Pad32)") (class "Default")
      (node (ref "IC1") (pin "32") (pinfunction "AREF_32") (pintype "bidirectional"))
    )
    (net (code "97") (name "unconnected-(J2-RCT-Pad3)") (class "Default")
      (node (ref "J2") (pin "3") (pinfunction "RCT_3") (pintype "bidirectional"))
    )
    (net (code "98") (name "unconnected-(J2-SHIELD-PadM1)") (class "Default")
      (node (ref "J2") (pin "M1") (pinfunction "SHIELD_M1") (pintype "bidirectional"))
    )
    (net (code "99") (name "unconnected-(J2-SHIELD-PadM2)") (class "Default")
      (node (ref "J2") (pin "M2") (pinfunction "SHIELD_M2") (pintype "bidirectional"))
    )
    (net (code "100") (name "unconnected-(U$2-BAS-Pad6)") (class "Default")
      (node (ref "U$2") (pin "6") (pinfunction "BAS_6") (pintype "passive"))
    )
    (net (code "101") (name "unconnected-(U$3-BAS-Pad6)") (class "Default")
      (node (ref "U$3") (pin "6") (pinfunction "BAS_6") (pintype "passive"))
    )
    (net (code "102") (name "unconnected-(U$4-BAS-Pad6)") (class "Default")
      (node (ref "U$4") (pin "6") (pinfunction "BAS_6") (pintype "passive"))
    )
    (net (code "103") (name "unconnected-(U$5-BAS-Pad6)") (class "Default")
      (node (ref "U$5") (pin "6") (pinfunction "BAS_6") (pintype "passive"))
    )
    (net (code "104") (name "unconnected-(U$6-BAS-Pad6)") (class "Default")
      (node (ref "U$6") (pin "6") (pinfunction "BAS_6") (pintype "passive"))
    )
    (net (code "105") (name "unconnected-(U$7-BAS-Pad6)") (class "Default")
      (node (ref "U$7") (pin "6") (pinfunction "BAS_6") (pintype "passive"))
    )
    (net (code "106") (name "unconnected-(U$8-BAS-Pad6)") (class "Default")
      (node (ref "U$8") (pin "6") (pinfunction "BAS_6") (pintype "passive"))
    )
    (net (code "107") (name "unconnected-(U$9-BAS-Pad6)") (class "Default")
      (node (ref "U$9") (pin "6") (pinfunction "BAS_6") (pintype "passive"))
    )
    (net (code "108") (name "unconnected-(U1-3V3OUT-Pad17)") (class "Default")
      (node (ref "U1") (pin "17") (pinfunction "3V3OUT_17") (pintype "output"))
    )
    (net (code "109") (name "unconnected-(U1-DCD-Pad10)") (class "Default")
      (node (ref "U1") (pin "10") (pinfunction "DCD_10") (pintype "input"))
    )
    (net (code "110") (name "unconnected-(U1-DSR-Pad9)") (class "Default")
      (node (ref "U1") (pin "9") (pinfunction "DSR_9") (pintype "input"))
    )
    (net (code "111") (name "unconnected-(U1-OSCI-Pad27)") (class "Default")
      (node (ref "U1") (pin "27") (pinfunction "OSCI_27") (pintype "input"))
    )
    (net (code "112") (name "unconnected-(U1-OSCO-Pad28)") (class "Default")
      (node (ref "U1") (pin "28") (pinfunction "OSCO_28") (pintype "output"))
    )
    (net (code "113") (name "unconnected-(U1-PWREN-Pad14)") (class "Default")
      (node (ref "U1") (pin "14") (pinfunction "PWREN_14") (pintype "input"))
    )
    (net (code "114") (name "unconnected-(U1-RESET-Pad19)") (class "Default")
      (node (ref "U1") (pin "19") (pinfunction "RESET_19") (pintype "input"))
    )
    (net (code "115") (name "unconnected-(U1-RI-Pad6)") (class "Default")
      (node (ref "U1") (pin "6") (pinfunction "RI_6") (pintype "input"))
    )
    (net (code "116") (name "unconnected-(U1-RXLED-Pad22)") (class "Default")
      (node (ref "U1") (pin "22") (pinfunction "RXLED_22") (pintype "input"))
    )
    (net (code "117") (name "unconnected-(U1-SLEEP-Pad12)") (class "Default")
      (node (ref "U1") (pin "12") (pinfunction "SLEEP_12") (pintype "input"))
    )
    (net (code "118") (name "unconnected-(U1-TXDEN-Pad13)") (class "Default")
      (node (ref "U1") (pin "13") (pinfunction "TXDEN_13") (pintype "input"))
    )
    (net (code "119") (name "unconnected-(U1-TXLED-Pad23)") (class "Default")
      (node (ref "U1") (pin "23") (pinfunction "TXLED_23") (pintype "input"))
    )
    (net (code "120") (name "unconnected-(U3-NC-Pad5)") (class "Default")
      (node (ref "U3") (pin "5") (pinfunction "NC_5") (pintype "bidirectional"))
    )
  )
)
